# Bolt-On_Template.net
KiCad netlist of a schematic drawn in EAGLE
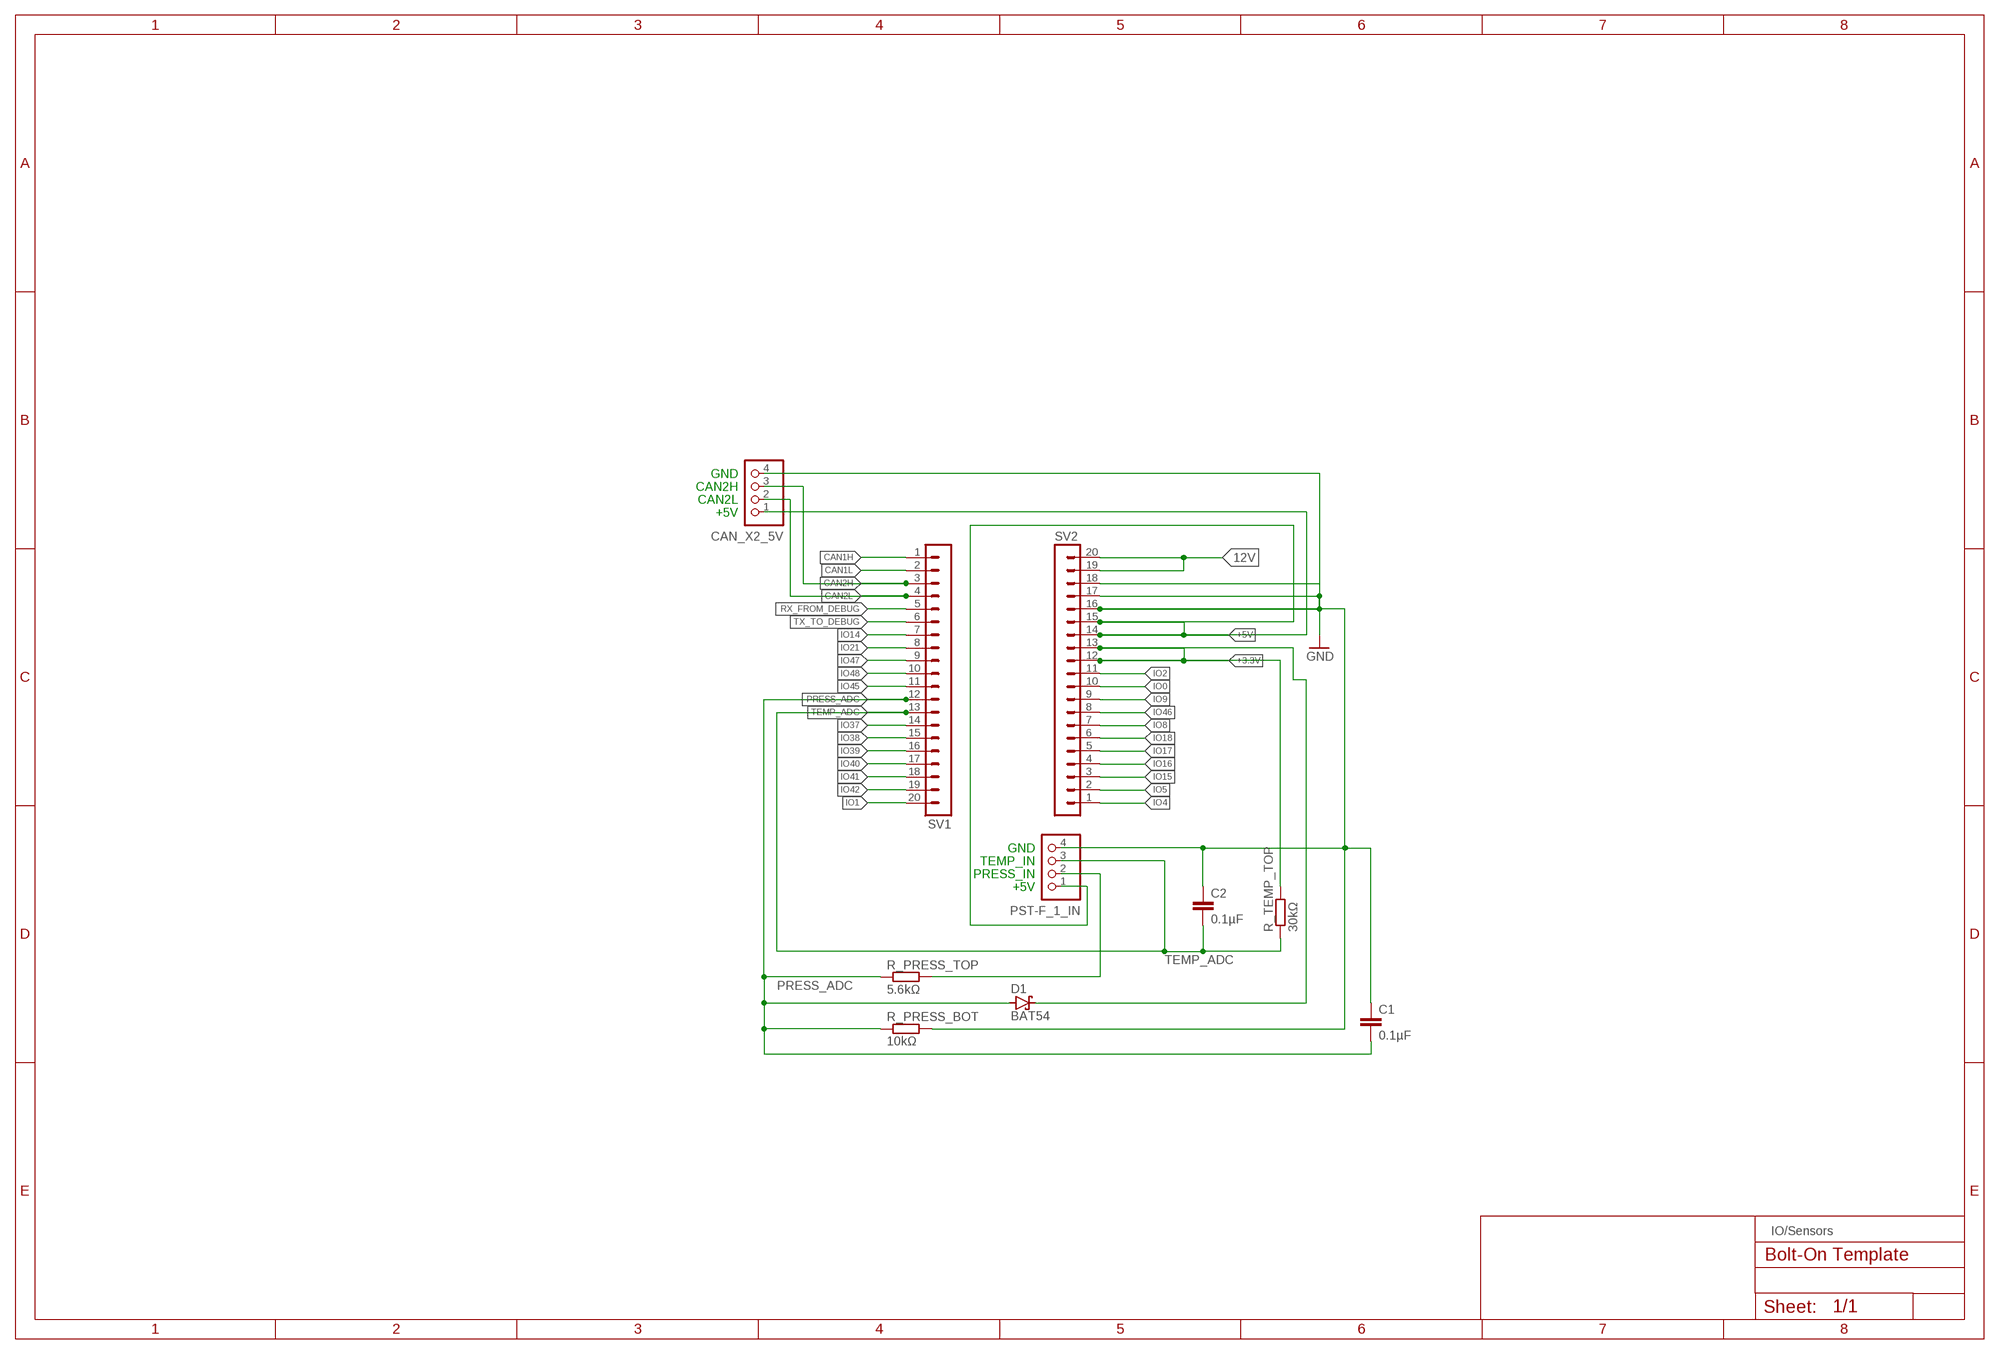
[diagram p0: schematic, sheet 1]

(export (version "E")
  (design (tool "Eeschema 10.0.6"))
  (components
    (comp (ref "C1")
      (value "0.1µF")
      (footprint "eagle-import:C0805")
      (libsource (lib "eagle-import") (part "C-EUC0805"))
    )
    (comp (ref "C2")
      (value "0.1µF")
      (footprint "eagle-import:C0805")
      (libsource (lib "eagle-import") (part "C-EUC0805"))
    )
    (comp (ref "CAN_X2_5V")
      (value "S4B-PH-K-S")
      (footprint "eagle-import:S4B-PH-K-S")
      (libsource (lib "eagle-import") (part "S4B-PH-K-S"))
    )
    (comp (ref "D1")
      (value "BAT54")
      (footprint "eagle-import:SOT23")
      (libsource (lib "eagle-import") (part "BAT54"))
    )
    (comp (ref "PST-F_1_IN")
      (value "S4B-PH-K-S")
      (footprint "eagle-import:S4B-PH-K-S")
      (libsource (lib "eagle-import") (part "S4B-PH-K-S"))
    )
    (comp (ref "R_PRESS_BOT")
      (value "10kΩ")
      (footprint "eagle-import:R0805")
      (libsource (lib "eagle-import") (part "R-EU_R0805"))
    )
    (comp (ref "R_PRESS_TOP")
      (value "5.6kΩ")
      (footprint "eagle-import:R0805")
      (libsource (lib "eagle-import") (part "R-EU_R0805"))
    )
    (comp (ref "R_TEMP_TOP")
      (value "30kΩ")
      (footprint "eagle-import:R0805")
      (libsource (lib "eagle-import") (part "R-EU_R0805"))
    )
    (comp (ref "SV1")
      (value "MA20-1L")
      (footprint "eagle-import:MA20-1L")
      (libsource (lib "eagle-import") (part "MA20-1L"))
    )
    (comp (ref "SV2")
      (value "MA20-1L")
      (footprint "eagle-import:MA20-1L")
      (libsource (lib "eagle-import") (part "MA20-1L"))
    )
  )
  (nets
    (net (code "1") (name "+3.3V") (class "Default")
      (node (ref "D1") (pin "3") (pinfunction "C_3") (pintype "passive"))
      (node (ref "R_TEMP_TOP") (pin "2") (pinfunction "2_2") (pintype "passive"))
      (node (ref "SV2") (pin "12") (pinfunction "12_12") (pintype "passive"))
      (node (ref "SV2") (pin "13") (pinfunction "13_13") (pintype "passive"))
    )
    (net (code "2") (name "+5V") (class "Default")
      (node (ref "CAN_X2_5V") (pin "1") (pinfunction "1_1") (pintype "passive"))
      (node (ref "PST-F_1_IN") (pin "1") (pinfunction "1_1") (pintype "passive"))
      (node (ref "SV2") (pin "14") (pinfunction "14_14") (pintype "passive"))
      (node (ref "SV2") (pin "15") (pinfunction "15_15") (pintype "passive"))
    )
    (net (code "3") (name "12V") (class "Default")
      (node (ref "SV2") (pin "19") (pinfunction "19_19") (pintype "passive"))
      (node (ref "SV2") (pin "20") (pinfunction "20_20") (pintype "passive"))
    )
    (net (code "4") (name "CAN1H") (class "Default")
      (node (ref "SV1") (pin "1") (pinfunction "1_1") (pintype "passive"))
    )
    (net (code "5") (name "CAN1L") (class "Default")
      (node (ref "SV1") (pin "2") (pinfunction "2_2") (pintype "passive"))
    )
    (net (code "6") (name "CAN2H") (class "Default")
      (node (ref "CAN_X2_5V") (pin "3") (pinfunction "3_3") (pintype "passive"))
      (node (ref "SV1") (pin "3") (pinfunction "3_3") (pintype "passive"))
    )
    (net (code "7") (name "CAN2L") (class "Default")
      (node (ref "CAN_X2_5V") (pin "2") (pinfunction "2_2") (pintype "passive"))
      (node (ref "SV1") (pin "4") (pinfunction "4_4") (pintype "passive"))
    )
    (net (code "8") (name "GND") (class "Default")
      (node (ref "C1") (pin "1") (pinfunction "1_1") (pintype "passive"))
      (node (ref "C2") (pin "1") (pinfunction "1_1") (pintype "passive"))
      (node (ref "CAN_X2_5V") (pin "4") (pinfunction "4_4") (pintype "passive"))
      (node (ref "PST-F_1_IN") (pin "4") (pinfunction "4_4") (pintype "passive"))
      (node (ref "R_PRESS_BOT") (pin "2") (pinfunction "2_2") (pintype "passive"))
      (node (ref "SV2") (pin "16") (pinfunction "16_16") (pintype "passive"))
      (node (ref "SV2") (pin "17") (pinfunction "17_17") (pintype "passive"))
      (node (ref "SV2") (pin "18") (pinfunction "18_18") (pintype "passive"))
    )
    (net (code "9") (name "IO0") (class "Default")
      (node (ref "SV2") (pin "10") (pinfunction "10_10") (pintype "passive"))
    )
    (net (code "10") (name "IO1") (class "Default")
      (node (ref "SV1") (pin "20") (pinfunction "20_20") (pintype "passive"))
    )
    (net (code "11") (name "IO2") (class "Default")
      (node (ref "SV2") (pin "11") (pinfunction "11_11") (pintype "passive"))
    )
    (net (code "12") (name "IO4") (class "Default")
      (node (ref "SV2") (pin "1") (pinfunction "1_1") (pintype "passive"))
    )
    (net (code "13") (name "IO5") (class "Default")
      (node (ref "SV2") (pin "2") (pinfunction "2_2") (pintype "passive"))
    )
    (net (code "14") (name "IO8") (class "Default")
      (node (ref "SV2") (pin "7") (pinfunction "7_7") (pintype "passive"))
    )
    (net (code "15") (name "IO9") (class "Default")
      (node (ref "SV2") (pin "9") (pinfunction "9_9") (pintype "passive"))
    )
    (net (code "16") (name "IO14") (class "Default")
      (node (ref "SV1") (pin "7") (pinfunction "7_7") (pintype "passive"))
    )
    (net (code "17") (name "IO15") (class "Default")
      (node (ref "SV2") (pin "3") (pinfunction "3_3") (pintype "passive"))
    )
    (net (code "18") (name "IO16") (class "Default")
      (node (ref "SV2") (pin "4") (pinfunction "4_4") (pintype "passive"))
    )
    (net (code "19") (name "IO17") (class "Default")
      (node (ref "SV2") (pin "5") (pinfunction "5_5") (pintype "passive"))
    )
    (net (code "20") (name "IO18") (class "Default")
      (node (ref "SV2") (pin "6") (pinfunction "6_6") (pintype "passive"))
    )
    (net (code "21") (name "IO21") (class "Default")
      (node (ref "SV1") (pin "8") (pinfunction "8_8") (pintype "passive"))
    )
    (net (code "22") (name "IO37") (class "Default")
      (node (ref "SV1") (pin "14") (pinfunction "14_14") (pintype "passive"))
    )
    (net (code "23") (name "IO38") (class "Default")
      (node (ref "SV1") (pin "15") (pinfunction "15_15") (pintype "passive"))
    )
    (net (code "24") (name "IO39") (class "Default")
      (node (ref "SV1") (pin "16") (pinfunction "16_16") (pintype "passive"))
    )
    (net (code "25") (name "IO40") (class "Default")
      (node (ref "SV1") (pin "17") (pinfunction "17_17") (pintype "passive"))
    )
    (net (code "26") (name "IO41") (class "Default")
      (node (ref "SV1") (pin "18") (pinfunction "18_18") (pintype "passive"))
    )
    (net (code "27") (name "IO42") (class "Default")
      (node (ref "SV1") (pin "19") (pinfunction "19_19") (pintype "passive"))
    )
    (net (code "28") (name "IO45") (class "Default")
      (node (ref "SV1") (pin "11") (pinfunction "11_11") (pintype "passive"))
    )
    (net (code "29") (name "IO46") (class "Default")
      (node (ref "SV2") (pin "8") (pinfunction "8_8") (pintype "passive"))
    )
    (net (code "30") (name "IO47") (class "Default")
      (node (ref "SV1") (pin "9") (pinfunction "9_9") (pintype "passive"))
    )
    (net (code "31") (name "IO48") (class "Default")
      (node (ref "SV1") (pin "10") (pinfunction "10_10") (pintype "passive"))
    )
    (net (code "32") (name "Net-(PST-F_1_IN-Pad2)") (class "Default")
      (node (ref "PST-F_1_IN") (pin "2") (pinfunction "2_2") (pintype "passive"))
      (node (ref "R_PRESS_TOP") (pin "2") (pinfunction "2_2") (pintype "passive"))
    )
    (net (code "33") (name "PRESS_ADC") (class "Default")
      (node (ref "C1") (pin "2") (pinfunction "2_2") (pintype "passive"))
      (node (ref "D1") (pin "1") (pinfunction "A_1") (pintype "passive"))
      (node (ref "R_PRESS_BOT") (pin "1") (pinfunction "1_1") (pintype "passive"))
      (node (ref "R_PRESS_TOP") (pin "1") (pinfunction "1_1") (pintype "passive"))
      (node (ref "SV1") (pin "12") (pinfunction "12_12") (pintype "passive"))
    )
    (net (code "34") (name "RX_FROM_DEBUG") (class "Default")
      (node (ref "SV1") (pin "5") (pinfunction "5_5") (pintype "passive"))
    )
    (net (code "35") (name "TEMP_ADC") (class "Default")
      (node (ref "C2") (pin "2") (pinfunction "2_2") (pintype "passive"))
      (node (ref "PST-F_1_IN") (pin "3") (pinfunction "3_3") (pintype "passive"))
      (node (ref "R_TEMP_TOP") (pin "1") (pinfunction "1_1") (pintype "passive"))
      (node (ref "SV1") (pin "13") (pinfunction "13_13") (pintype "passive"))
    )
    (net (code "36") (name "TX_TO_DEBUG") (class "Default")
      (node (ref "SV1") (pin "6") (pinfunction "6_6") (pintype "passive"))
    )
  )
)
